# Block-Diagram.net
KiCad netlist of a schematic drawn in Altium Designer
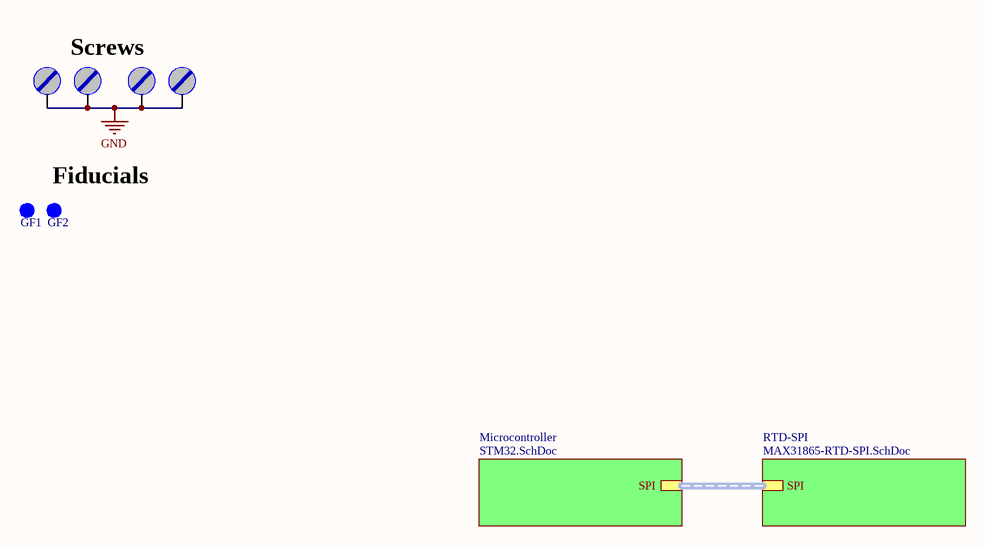
[diagram p0: Block-Diagram.SchDoc]

(export (version "E")
  (design (tool "Eeschema 10.0.6"))
  (components
    (comp (ref "GF1")
      (value "Fiducial")
      (footprint "FIDUCIAL 1mm")
      (description "Guia Fiducial")
      (libsource (lib "Tecnoclade") (part "Fiducial"))
    )
    (comp (ref "GF2")
      (value "Fiducial")
      (footprint "FIDUCIAL 1mm")
      (description "Guia Fiducial")
      (libsource (lib "Tecnoclade") (part "Fiducial"))
    )
    (comp (ref "M1")
      (value "Furo de Fixação")
      (footprint "Furo_M3")
      (description "Furo para parafuso")
      (libsource (lib "Tecnoclade") (part "Parafuso"))
    )
    (comp (ref "M2")
      (value "Furo de Fixação")
      (footprint "Furo_M3")
      (description "Furo para parafuso")
      (libsource (lib "Tecnoclade") (part "Parafuso"))
    )
    (comp (ref "M3")
      (value "Furo de Fixação")
      (footprint "Furo_M3")
      (description "Furo para parafuso")
      (libsource (lib "Tecnoclade") (part "Parafuso"))
    )
    (comp (ref "M4")
      (value "Furo de Fixação")
      (footprint "Furo_M3")
      (description "Furo para parafuso")
      (libsource (lib "Tecnoclade") (part "Parafuso"))
    )
  )
  (nets
    (net (code "2") (name "GND") (class "Default")
      (node (ref "M1") (pin "X") (pinfunction "X_X") (pintype "passive"))
      (node (ref "M2") (pin "X") (pinfunction "X_X") (pintype "passive"))
      (node (ref "M3") (pin "X") (pinfunction "X_X") (pintype "passive"))
      (node (ref "M4") (pin "X") (pinfunction "X_X") (pintype "passive"))
    )
  )
)
